# 01_USB.net
KiCad netlist of a schematic drawn in Altium Designer
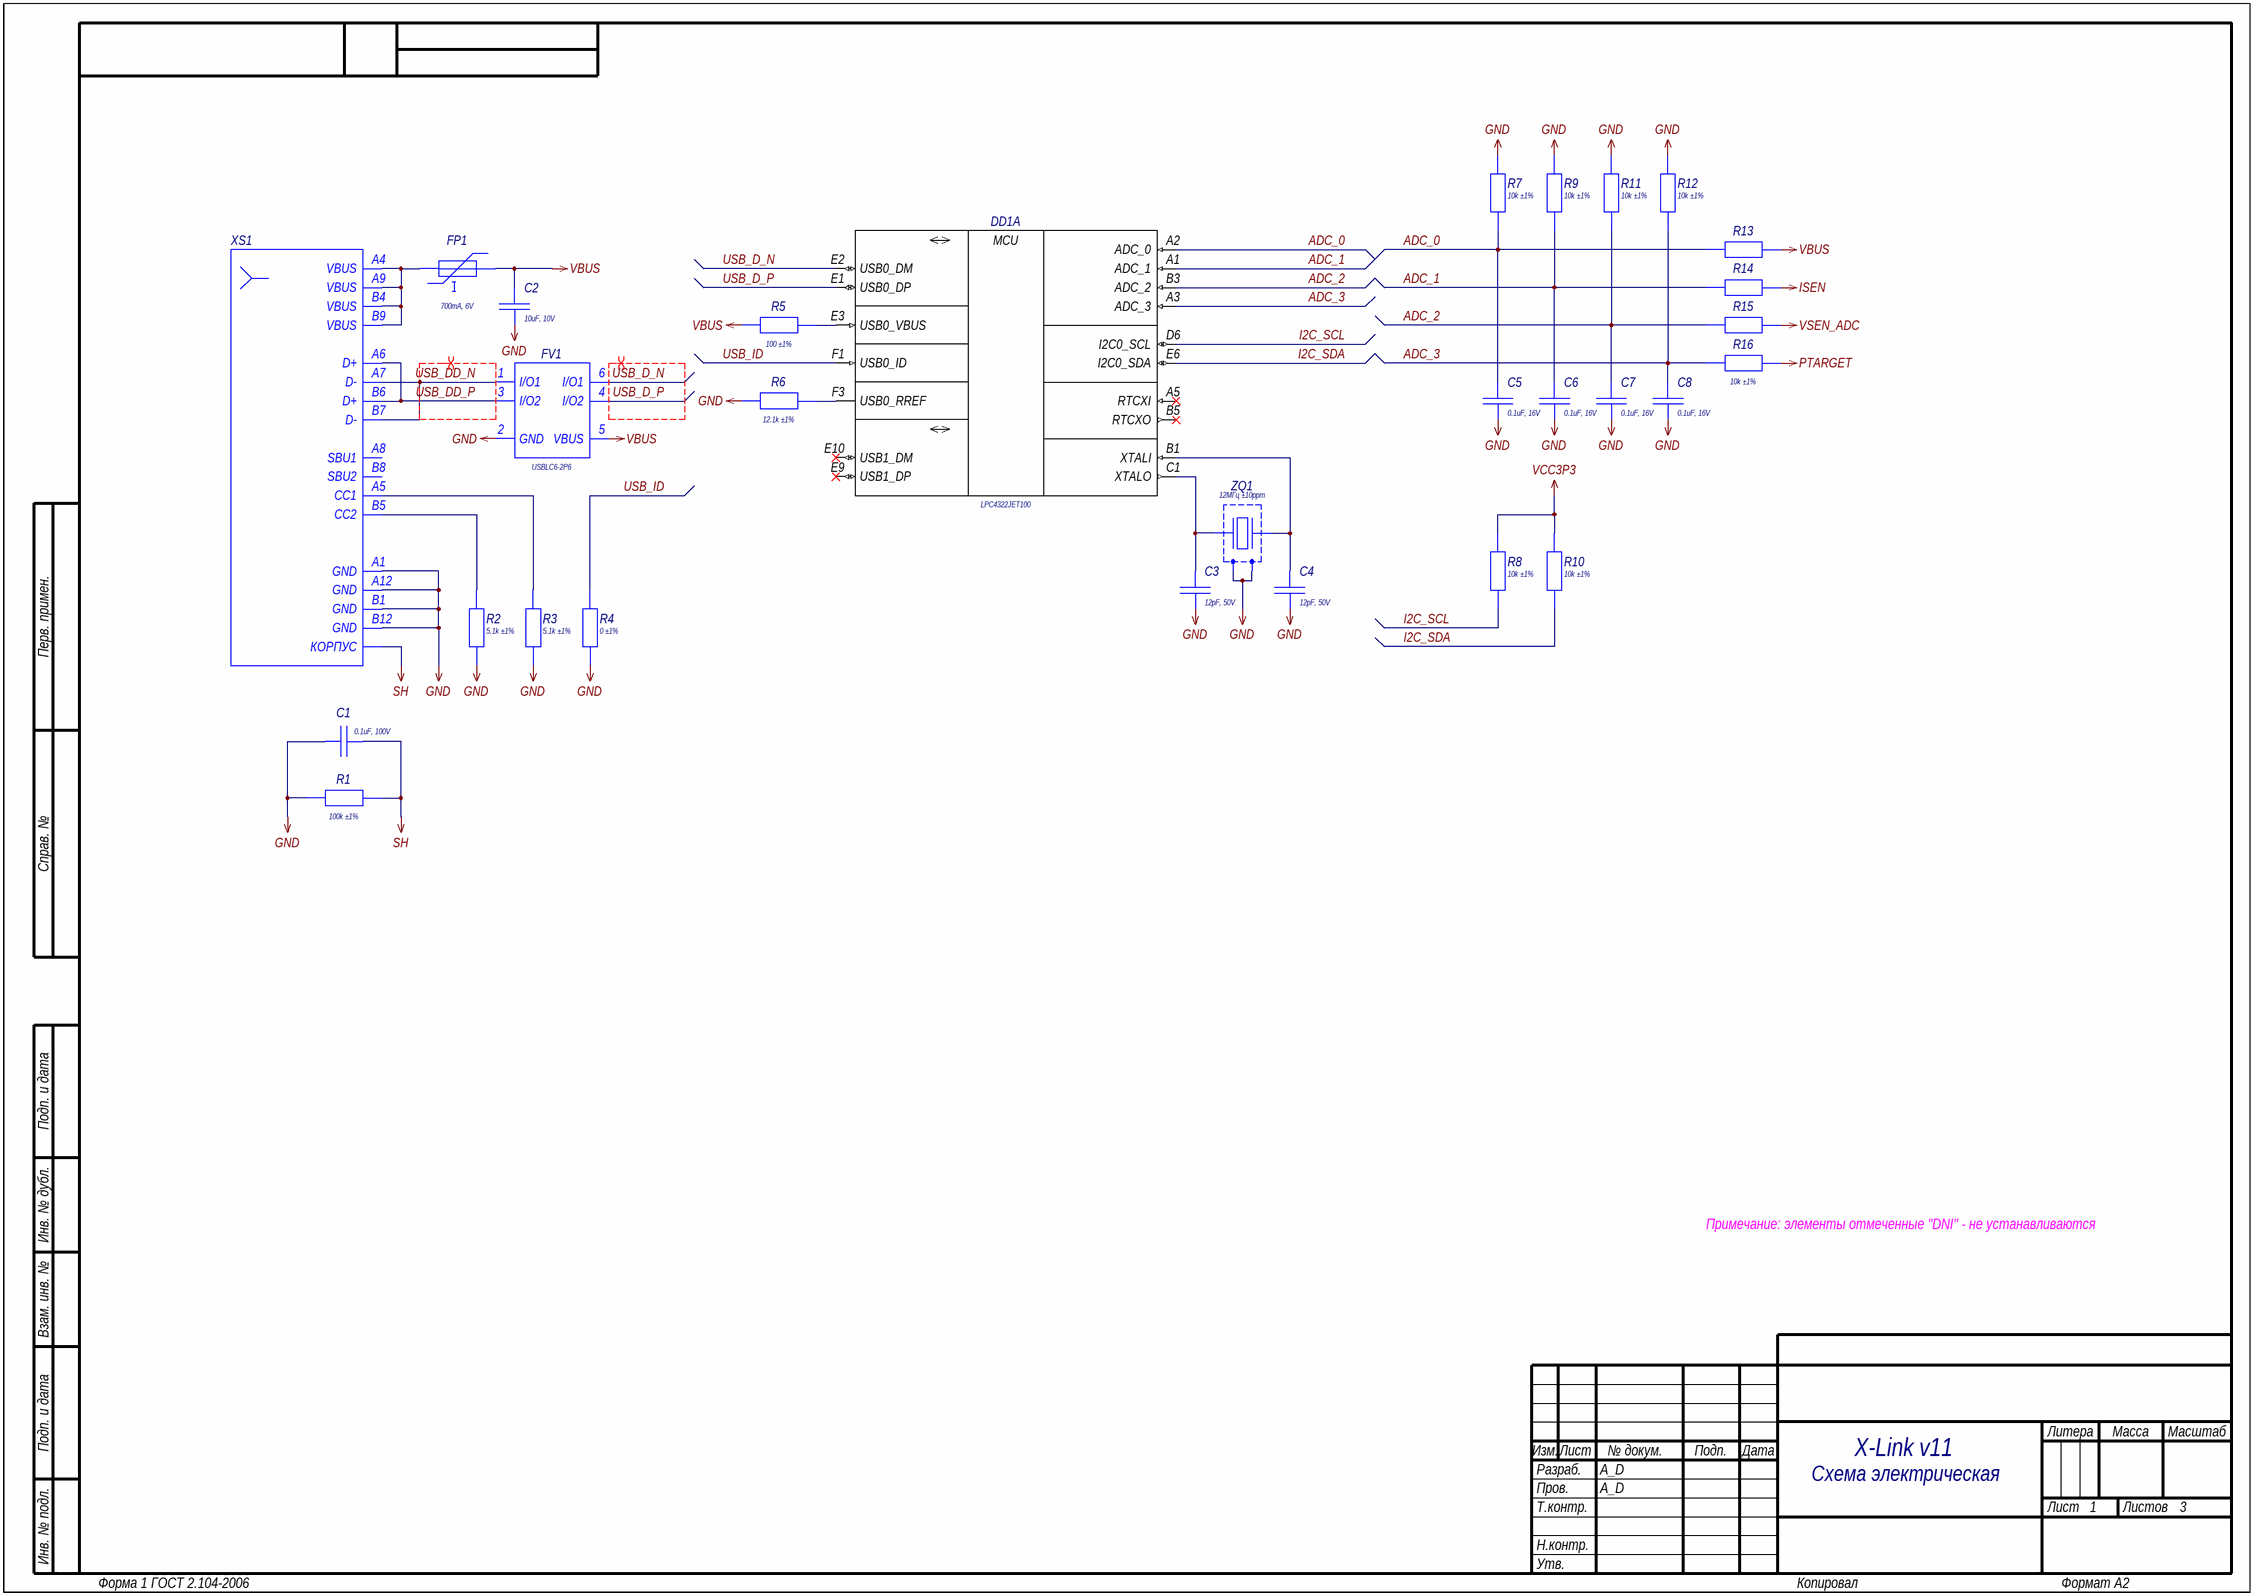
[diagram p0: 01_USB.SchDoc]

(export (version "E")
  (design (tool "Eeschema 10.0.6"))
  (components
    (comp (ref "C1")
      (value "Capacitor")
      (footprint "C0603_160X080H080_H")
      (fields
        (field (name "PART NUMBER") "GRM188R72A104KA35D")
        (field (name "VOLTAGE") "100V")
        (field (name "TOLERANCE") "±10%")
        (field (name "SCHEMATIC VALUE") "0.1uF, 100V")
      )
      (libsource (lib "ADLib") (part "Capacitor"))
    )
    (comp (ref "C2")
      (value "Capacitor")
      (footprint "C0603_160X080H080_H")
      (fields
        (field (name "PART NUMBER") "GRM188R61A106KE69D")
        (field (name "VOLTAGE") "10V")
        (field (name "TOLERANCE") "±10%")
        (field (name "SCHEMATIC VALUE") "10uF, 10V")
      )
      (libsource (lib "ADLib") (part "Capacitor"))
    )
    (comp (ref "C3")
      (value "Capacitor")
      (footprint "C0402_100X050H050_H")
      (fields
        (field (name "PART NUMBER") "GRM1555C1H120JA01D")
        (field (name "VOLTAGE") "50V")
        (field (name "TOLERANCE") "±5%")
        (field (name "SCHEMATIC VALUE") "12pF, 50V")
      )
      (libsource (lib "ADLib") (part "Capacitor"))
    )
    (comp (ref "C4")
      (value "Capacitor")
      (footprint "C0402_100X050H050_H")
      (fields
        (field (name "PART NUMBER") "GRM1555C1H120JA01D")
        (field (name "VOLTAGE") "50V")
        (field (name "TOLERANCE") "±5%")
        (field (name "SCHEMATIC VALUE") "12pF, 50V")
      )
      (libsource (lib "ADLib") (part "Capacitor"))
    )
    (comp (ref "C5")
      (value "Capacitor")
      (footprint "C0402_100X050H050_H")
      (fields
        (field (name "PART NUMBER") "GCM155R71C104KA55D")
        (field (name "VOLTAGE") "16V")
        (field (name "TOLERANCE") "±10%")
        (field (name "SCHEMATIC VALUE") "0.1uF, 16V")
      )
      (libsource (lib "ADLib") (part "Capacitor"))
    )
    (comp (ref "C6")
      (value "Capacitor")
      (footprint "C0402_100X050H050_H")
      (fields
        (field (name "PART NUMBER") "GCM155R71C104KA55D")
        (field (name "VOLTAGE") "16V")
        (field (name "TOLERANCE") "±10%")
        (field (name "SCHEMATIC VALUE") "0.1uF, 16V")
      )
      (libsource (lib "ADLib") (part "Capacitor"))
    )
    (comp (ref "C7")
      (value "Capacitor")
      (footprint "C0402_100X050H050_H")
      (fields
        (field (name "PART NUMBER") "GCM155R71C104KA55D")
        (field (name "VOLTAGE") "16V")
        (field (name "TOLERANCE") "±10%")
        (field (name "SCHEMATIC VALUE") "0.1uF, 16V")
      )
      (libsource (lib "ADLib") (part "Capacitor"))
    )
    (comp (ref "C8")
      (value "Capacitor")
      (footprint "C0402_100X050H050_H")
      (fields
        (field (name "PART NUMBER") "GCM155R71C104KA55D")
        (field (name "VOLTAGE") "16V")
        (field (name "TOLERANCE") "±10%")
        (field (name "SCHEMATIC VALUE") "0.1uF, 16V")
      )
      (libsource (lib "ADLib") (part "Capacitor"))
    )
    (comp (ref "DD1")
      (value "LPC43xxJET100-Series")
      (footprint "TFBGA-100_080P900X900X120_N")
      (fields
        (field (name "SCHEMATIC VALUE") "LPC4322JET100")
        (field (name "PART NUMBER") "LPC4322JET100")
        (field (name "MANUFACTURER") "NXP Semiconductors")
      )
      (libsource (lib "ADLib") (part "LPC43xxJET100-Series"))
    )
    (comp (ref "FP1")
      (value "Fuse_PTC")
      (footprint "F0402_115X065H060_H")
      (fields
        (field (name "PART NUMBER") "0402L035SLKR")
        (field (name "MANUFACTURER") "Littelfuse")
        (field (name "SCHEMATIC VALUE") "700mA, 6V")
      )
      (libsource (lib "ADLib") (part "Fuse_PTC"))
    )
    (comp (ref "FV1")
      (value "USBLC6-2x6")
      (footprint "SOT-666_050P160X120X060_N")
      (fields
        (field (name "PART NUMBER") "USBLC6-2P6")
        (field (name "LCSC PART") "C15999")
        (field (name "MANUFACTURER") "STMicroelectronics")
        (field (name "SCHEMATIC VALUE") "USBLC6-2P6")
      )
      (libsource (lib "ADLib") (part "USBLC6-2x6"))
    )
    (comp (ref "R1")
      (value "Resistor")
      (footprint "R0402_100X050H035_H")
      (fields
        (field (name "PART NUMBER") "0402WGF1003TCE")
        (field (name "TOLERANCE") "±1%")
        (field (name "MANUFACTURER") "Uniroyal Elec")
        (field (name "SCHEMATIC VALUE") "100k ±1%")
      )
      (libsource (lib "ADLib") (part "Resistor"))
    )
    (comp (ref "R2")
      (value "Resistor")
      (footprint "R0402_100X050H035_H")
      (fields
        (field (name "PART NUMBER") "0402WGF5101TCE")
        (field (name "TOLERANCE") "±1%")
        (field (name "MANUFACTURER") "Uniroyal Elec")
        (field (name "SCHEMATIC VALUE") "5.1k ±1%")
      )
      (libsource (lib "ADLib") (part "Resistor"))
    )
    (comp (ref "R3")
      (value "Resistor")
      (footprint "R0402_100X050H035_H")
      (fields
        (field (name "PART NUMBER") "0402WGF5101TCE")
        (field (name "TOLERANCE") "±1%")
        (field (name "MANUFACTURER") "Uniroyal Elec")
        (field (name "SCHEMATIC VALUE") "5.1k ±1%")
      )
      (libsource (lib "ADLib") (part "Resistor"))
    )
    (comp (ref "R4")
      (value "Resistor")
      (footprint "R0402_100X050H035_H")
      (fields
        (field (name "PART NUMBER") "0402WGF0000TCE")
        (field (name "TOLERANCE") "±1%")
        (field (name "MANUFACTURER") "Uniroyal Elec")
        (field (name "SCHEMATIC VALUE") "0 ±1%")
      )
      (libsource (lib "ADLib") (part "Resistor"))
    )
    (comp (ref "R5")
      (value "Resistor")
      (footprint "R0402_100X050H035_H")
      (fields
        (field (name "PART NUMBER") "RC0402FR-07100RL")
        (field (name "TOLERANCE") "±1%")
        (field (name "MANUFACTURER") "Yageo")
        (field (name "SCHEMATIC VALUE") "100 ±1%")
      )
      (libsource (lib "ADLib") (part "Resistor"))
    )
    (comp (ref "R6")
      (value "Resistor")
      (footprint "R0402_100X050H035_H")
      (fields
        (field (name "PART NUMBER") "RC0402FR-0712K1L")
        (field (name "TOLERANCE") "±1%")
        (field (name "MANUFACTURER") "Yageo")
        (field (name "SCHEMATIC VALUE") "12.1k ±1%")
      )
      (libsource (lib "ADLib") (part "Resistor"))
    )
    (comp (ref "R7")
      (value "Resistor")
      (footprint "R0402_100X050H035_H")
      (fields
        (field (name "PART NUMBER") "0402WGF1002TCE")
        (field (name "TOLERANCE") "±1%")
        (field (name "MANUFACTURER") "Uniroyal Elec")
        (field (name "SCHEMATIC VALUE") "10k ±1%")
      )
      (libsource (lib "ADLib") (part "Resistor"))
    )
    (comp (ref "R8")
      (value "Resistor")
      (footprint "R0402_100X050H035_H")
      (fields
        (field (name "PART NUMBER") "0402WGF1002TCE")
        (field (name "TOLERANCE") "±1%")
        (field (name "MANUFACTURER") "Uniroyal Elec")
        (field (name "SCHEMATIC VALUE") "10k ±1%")
      )
      (libsource (lib "ADLib") (part "Resistor"))
    )
    (comp (ref "R9")
      (value "Resistor")
      (footprint "R0402_100X050H035_H")
      (fields
        (field (name "PART NUMBER") "0402WGF1002TCE")
        (field (name "TOLERANCE") "±1%")
        (field (name "MANUFACTURER") "Uniroyal Elec")
        (field (name "SCHEMATIC VALUE") "10k ±1%")
      )
      (libsource (lib "ADLib") (part "Resistor"))
    )
    (comp (ref "R10")
      (value "Resistor")
      (footprint "R0402_100X050H035_H")
      (fields
        (field (name "PART NUMBER") "0402WGF1002TCE")
        (field (name "TOLERANCE") "±1%")
        (field (name "MANUFACTURER") "Uniroyal Elec")
        (field (name "SCHEMATIC VALUE") "10k ±1%")
      )
      (libsource (lib "ADLib") (part "Resistor"))
    )
    (comp (ref "R11")
      (value "Resistor")
      (footprint "R0402_100X050H035_H")
      (fields
        (field (name "PART NUMBER") "0402WGF1002TCE")
        (field (name "TOLERANCE") "±1%")
        (field (name "MANUFACTURER") "Uniroyal Elec")
        (field (name "SCHEMATIC VALUE") "10k ±1%")
      )
      (libsource (lib "ADLib") (part "Resistor"))
    )
    (comp (ref "R12")
      (value "Resistor")
      (footprint "R0402_100X050H035_H")
      (fields
        (field (name "PART NUMBER") "0402WGF1002TCE")
        (field (name "TOLERANCE") "±1%")
        (field (name "MANUFACTURER") "Uniroyal Elec")
        (field (name "SCHEMATIC VALUE") "10k ±1%")
      )
      (libsource (lib "ADLib") (part "Resistor"))
    )
    (comp (ref "R13")
      (value "Resistor")
      (footprint "R0402_100X050H035_H")
      (fields
        (field (name "PART NUMBER") "0402WGF1002TCE")
        (field (name "TOLERANCE") "±1%")
        (field (name "MANUFACTURER") "Uniroyal Elec")
      )
      (libsource (lib "ADLib") (part "Resistor"))
    )
    (comp (ref "R14")
      (value "Resistor")
      (footprint "R0402_100X050H035_H")
      (fields
        (field (name "PART NUMBER") "0402WGF1002TCE")
        (field (name "TOLERANCE") "±1%")
        (field (name "MANUFACTURER") "Uniroyal Elec")
      )
      (libsource (lib "ADLib") (part "Resistor"))
    )
    (comp (ref "R15")
      (value "Resistor")
      (footprint "R0402_100X050H035_H")
      (fields
        (field (name "PART NUMBER") "0402WGF1002TCE")
        (field (name "TOLERANCE") "±1%")
        (field (name "MANUFACTURER") "Uniroyal Elec")
      )
      (libsource (lib "ADLib") (part "Resistor"))
    )
    (comp (ref "R16")
      (value "Resistor")
      (footprint "R0402_100X050H035_H")
      (fields
        (field (name "PART NUMBER") "0402WGF1002TCE")
        (field (name "TOLERANCE") "±1%")
        (field (name "MANUFACTURER") "Uniroyal Elec")
        (field (name "SCHEMATIC VALUE") "10k ±1%")
      )
      (libsource (lib "ADLib") (part "Resistor"))
    )
    (comp (ref "XS1")
      (value "Text")
      (footprint "U262-161N-4BVC11")
      (fields
        (field (name "PART NUMBER") "U262-161N-4BVC11")
        (field (name "LCSC PART") "C319148")
        (field (name "MANUFACTURER") "XKB Enterprise")
      )
      (libsource (lib "ADLib") (part "Con-USB_C-F-16P"))
    )
    (comp (ref "ZQ1")
      (value "Crystal-1_3p_S")
      (footprint "SMD 3.2x2.5mm")
      (fields
        (field (name "PART NUMBER") "X322512MOB4SI")
        (field (name "LCSC PART") "C70565")
        (field (name "MANUFACTURER") "Yangxing Tech")
        (field (name "SCHEMATIC VALUE") "12МГц ±10ppm")
      )
      (libsource (lib "ADLib") (part "Crystal-1_3p_S"))
    )
  )
  (nets
    (net (code "1") (name "/ADC_0") (class "Default")
      (node (ref "C5") (pin "2") (pinfunction "2_2") (pintype "passive"))
      (node (ref "DD1") (pin "A2") (pinfunction "ADC_0_A2") (pintype "input"))
      (node (ref "R13") (pin "2") (pinfunction "2_2") (pintype "passive"))
      (node (ref "R7") (pin "2") (pinfunction "2_2") (pintype "passive"))
    )
    (net (code "2") (name "/ADC_1") (class "Default")
      (node (ref "C6") (pin "2") (pinfunction "2_2") (pintype "passive"))
      (node (ref "DD1") (pin "A1") (pinfunction "ADC_1_A1") (pintype "input"))
      (node (ref "R14") (pin "2") (pinfunction "2_2") (pintype "passive"))
      (node (ref "R9") (pin "2") (pinfunction "2_2") (pintype "passive"))
    )
    (net (code "3") (name "/ADC_2") (class "Default")
      (node (ref "C7") (pin "2") (pinfunction "2_2") (pintype "passive"))
      (node (ref "DD1") (pin "B3") (pinfunction "ADC_2_B3") (pintype "input"))
      (node (ref "R11") (pin "2") (pinfunction "2_2") (pintype "passive"))
      (node (ref "R15") (pin "2") (pinfunction "2_2") (pintype "passive"))
    )
    (net (code "4") (name "/ADC_3") (class "Default")
      (node (ref "C8") (pin "2") (pinfunction "2_2") (pintype "passive"))
      (node (ref "DD1") (pin "A3") (pinfunction "ADC_3_A3") (pintype "input"))
      (node (ref "R12") (pin "2") (pinfunction "2_2") (pintype "passive"))
      (node (ref "R16") (pin "2") (pinfunction "2_2") (pintype "passive"))
    )
    (net (code "5") (name "/I2C_SCL") (class "Default")
      (node (ref "DD1") (pin "D6") (pinfunction "I2C0_SCL_D6") (pintype "bidirectional"))
      (node (ref "R8") (pin "2") (pinfunction "2_2") (pintype "passive"))
    )
    (net (code "6") (name "/I2C_SDA") (class "Default")
      (node (ref "DD1") (pin "E6") (pinfunction "I2C0_SDA_E6") (pintype "bidirectional"))
      (node (ref "R10") (pin "2") (pinfunction "2_2") (pintype "passive"))
    )
    (net (code "7") (name "/USB_DD_N") (class "Default")
      (node (ref "FV1") (pin "1") (pinfunction "I/O1_1") (pintype "passive"))
      (node (ref "XS1") (pin "A7") (pinfunction "D-_A7") (pintype "passive"))
      (node (ref "XS1") (pin "B7") (pinfunction "D-_B7") (pintype "passive"))
    )
    (net (code "8") (name "/USB_DD_P") (class "Default")
      (node (ref "FV1") (pin "3") (pinfunction "I/O2_3") (pintype "passive"))
      (node (ref "XS1") (pin "A6") (pinfunction "D+_A6") (pintype "passive"))
      (node (ref "XS1") (pin "B6") (pinfunction "D+_B6") (pintype "passive"))
    )
    (net (code "9") (name "/USB_D_N") (class "Default")
      (node (ref "DD1") (pin "E2") (pinfunction "USB0_DM_E2") (pintype "bidirectional"))
      (node (ref "FV1") (pin "6") (pinfunction "I/O1_6") (pintype "passive"))
    )
    (net (code "10") (name "/USB_D_P") (class "Default")
      (node (ref "DD1") (pin "E1") (pinfunction "USB0_DP_E1") (pintype "bidirectional"))
      (node (ref "FV1") (pin "4") (pinfunction "I/O2_4") (pintype "passive"))
    )
    (net (code "11") (name "/USB_ID") (class "Default")
      (node (ref "DD1") (pin "F1") (pinfunction "USB0_ID_F1") (pintype "input"))
      (node (ref "R4") (pin "2") (pinfunction "2_2") (pintype "passive"))
    )
    (net (code "12") (name "GND") (class "Default")
      (node (ref "C1") (pin "2") (pinfunction "2_2") (pintype "passive"))
      (node (ref "C2") (pin "1") (pinfunction "1_1") (pintype "passive"))
      (node (ref "C3") (pin "1") (pinfunction "1_1") (pintype "passive"))
      (node (ref "C4") (pin "1") (pinfunction "1_1") (pintype "passive"))
      (node (ref "C5") (pin "1") (pinfunction "1_1") (pintype "passive"))
      (node (ref "C6") (pin "1") (pinfunction "1_1") (pintype "passive"))
      (node (ref "C7") (pin "1") (pinfunction "1_1") (pintype "passive"))
      (node (ref "C8") (pin "1") (pinfunction "1_1") (pintype "passive"))
      (node (ref "FV1") (pin "2") (pinfunction "GND_2") (pintype "passive"))
      (node (ref "R1") (pin "2") (pinfunction "2_2") (pintype "passive"))
      (node (ref "R11") (pin "1") (pinfunction "1_1") (pintype "passive"))
      (node (ref "R12") (pin "1") (pinfunction "1_1") (pintype "passive"))
      (node (ref "R2") (pin "1") (pinfunction "1_1") (pintype "passive"))
      (node (ref "R3") (pin "1") (pinfunction "1_1") (pintype "passive"))
      (node (ref "R4") (pin "1") (pinfunction "1_1") (pintype "passive"))
      (node (ref "R6") (pin "1") (pinfunction "1_1") (pintype "passive"))
      (node (ref "R7") (pin "1") (pinfunction "1_1") (pintype "passive"))
      (node (ref "R9") (pin "1") (pinfunction "1_1") (pintype "passive"))
      (node (ref "XS1") (pin "A1") (pinfunction "GND_A1") (pintype "passive"))
      (node (ref "XS1") (pin "A12") (pinfunction "GND_A12") (pintype "passive"))
      (node (ref "XS1") (pin "B1") (pinfunction "GND_B1") (pintype "passive"))
      (node (ref "XS1") (pin "B12") (pinfunction "GND_B12") (pintype "passive"))
      (node (ref "ZQ1") (pin "2") (pinfunction "2_2") (pintype "passive"))
      (node (ref "ZQ1") (pin "4") (pinfunction "4_4") (pintype "passive"))
    )
    (net (code "13") (name "ISEN") (class "Default")
      (node (ref "R14") (pin "1") (pinfunction "1_1") (pintype "passive"))
    )
    (net (code "14") (name "Net-(DD1A-USB0_RREF)") (class "Default")
      (node (ref "DD1") (pin "F3") (pinfunction "USB0_RREF_F3") (pintype "passive"))
      (node (ref "R6") (pin "2") (pinfunction "2_2") (pintype "passive"))
    )
    (net (code "15") (name "Net-(DD1A-USB0_VBUS)") (class "Default")
      (node (ref "DD1") (pin "E3") (pinfunction "USB0_VBUS_E3") (pintype "input"))
      (node (ref "R5") (pin "2") (pinfunction "2_2") (pintype "passive"))
    )
    (net (code "16") (name "Net-(DD1A-XTALI)") (class "Default")
      (node (ref "C4") (pin "2") (pinfunction "2_2") (pintype "passive"))
      (node (ref "DD1") (pin "B1") (pinfunction "XTALI_B1") (pintype "input"))
      (node (ref "ZQ1") (pin "3") (pinfunction "3_3") (pintype "passive"))
    )
    (net (code "17") (name "Net-(DD1A-XTALO)") (class "Default")
      (node (ref "C3") (pin "2") (pinfunction "2_2") (pintype "passive"))
      (node (ref "DD1") (pin "C1") (pinfunction "XTALO_C1") (pintype "output"))
      (node (ref "ZQ1") (pin "1") (pinfunction "1_1") (pintype "passive"))
    )
    (net (code "18") (name "Net-(FP1-Pad1)") (class "Default")
      (node (ref "FP1") (pin "1") (pinfunction "1_1") (pintype "passive"))
      (node (ref "XS1") (pin "A4") (pinfunction "VBUS_A4") (pintype "passive"))
      (node (ref "XS1") (pin "A9") (pinfunction "VBUS_A9") (pintype "passive"))
      (node (ref "XS1") (pin "B4") (pinfunction "VBUS_B4") (pintype "passive"))
      (node (ref "XS1") (pin "B9") (pinfunction "VBUS_B9") (pintype "passive"))
    )
    (net (code "19") (name "Net-(XS1-CC1)") (class "Default")
      (node (ref "R3") (pin "2") (pinfunction "2_2") (pintype "passive"))
      (node (ref "XS1") (pin "A5") (pinfunction "CC1_A5") (pintype "passive"))
    )
    (net (code "20") (name "Net-(XS1-CC2)") (class "Default")
      (node (ref "R2") (pin "2") (pinfunction "2_2") (pintype "passive"))
      (node (ref "XS1") (pin "B5") (pinfunction "CC2_B5") (pintype "passive"))
    )
    (net (code "21") (name "PTARGET") (class "Default")
      (node (ref "R16") (pin "1") (pinfunction "1_1") (pintype "passive"))
    )
    (net (code "22") (name "SH") (class "Default")
      (node (ref "C1") (pin "1") (pinfunction "1_1") (pintype "passive"))
      (node (ref "R1") (pin "1") (pinfunction "1_1") (pintype "passive"))
      (node (ref "XS1") (pin "SH") (pinfunction "КОРПУС_SH") (pintype "passive"))
    )
    (net (code "23") (name "VBUS") (class "Default")
      (node (ref "C2") (pin "2") (pinfunction "2_2") (pintype "passive"))
      (node (ref "FP1") (pin "2") (pinfunction "2_2") (pintype "passive"))
      (node (ref "FV1") (pin "5") (pinfunction "VBUS_5") (pintype "passive"))
      (node (ref "R13") (pin "1") (pinfunction "1_1") (pintype "passive"))
      (node (ref "R5") (pin "1") (pinfunction "1_1") (pintype "passive"))
    )
    (net (code "24") (name "VCC3P3") (class "Default")
      (node (ref "R10") (pin "1") (pinfunction "1_1") (pintype "passive"))
      (node (ref "R8") (pin "1") (pinfunction "1_1") (pintype "passive"))
    )
    (net (code "25") (name "VSEN_ADC") (class "Default")
      (node (ref "R15") (pin "1") (pinfunction "1_1") (pintype "passive"))
    )
    (net (code "26") (name "unconnected-(DD1A-RTCXI-PadA5)") (class "Default")
      (node (ref "DD1") (pin "A5") (pinfunction "RTCXI_A5") (pintype "input+no_connect"))
    )
    (net (code "27") (name "unconnected-(DD1A-RTCXO-PadB5)") (class "Default")
      (node (ref "DD1") (pin "B5") (pinfunction "RTCXO_B5") (pintype "output+no_connect"))
    )
    (net (code "28") (name "unconnected-(DD1A-USB1_DM-PadE10)") (class "Default")
      (node (ref "DD1") (pin "E10") (pinfunction "USB1_DM_E10") (pintype "bidirectional+no_connect"))
    )
    (net (code "29") (name "unconnected-(DD1A-USB1_DP-PadE9)") (class "Default")
      (node (ref "DD1") (pin "E9") (pinfunction "USB1_DP_E9") (pintype "bidirectional+no_connect"))
    )
    (net (code "30") (name "unconnected-(XS1-SBU1-PadA8)") (class "Default")
      (node (ref "XS1") (pin "A8") (pinfunction "SBU1_A8") (pintype "passive"))
    )
    (net (code "31") (name "unconnected-(XS1-SBU2-PadB8)") (class "Default")
      (node (ref "XS1") (pin "B8") (pinfunction "SBU2_B8") (pintype "passive"))
    )
  )
)
